# SEN00001.net
KiCad netlist of a schematic drawn in EAGLE
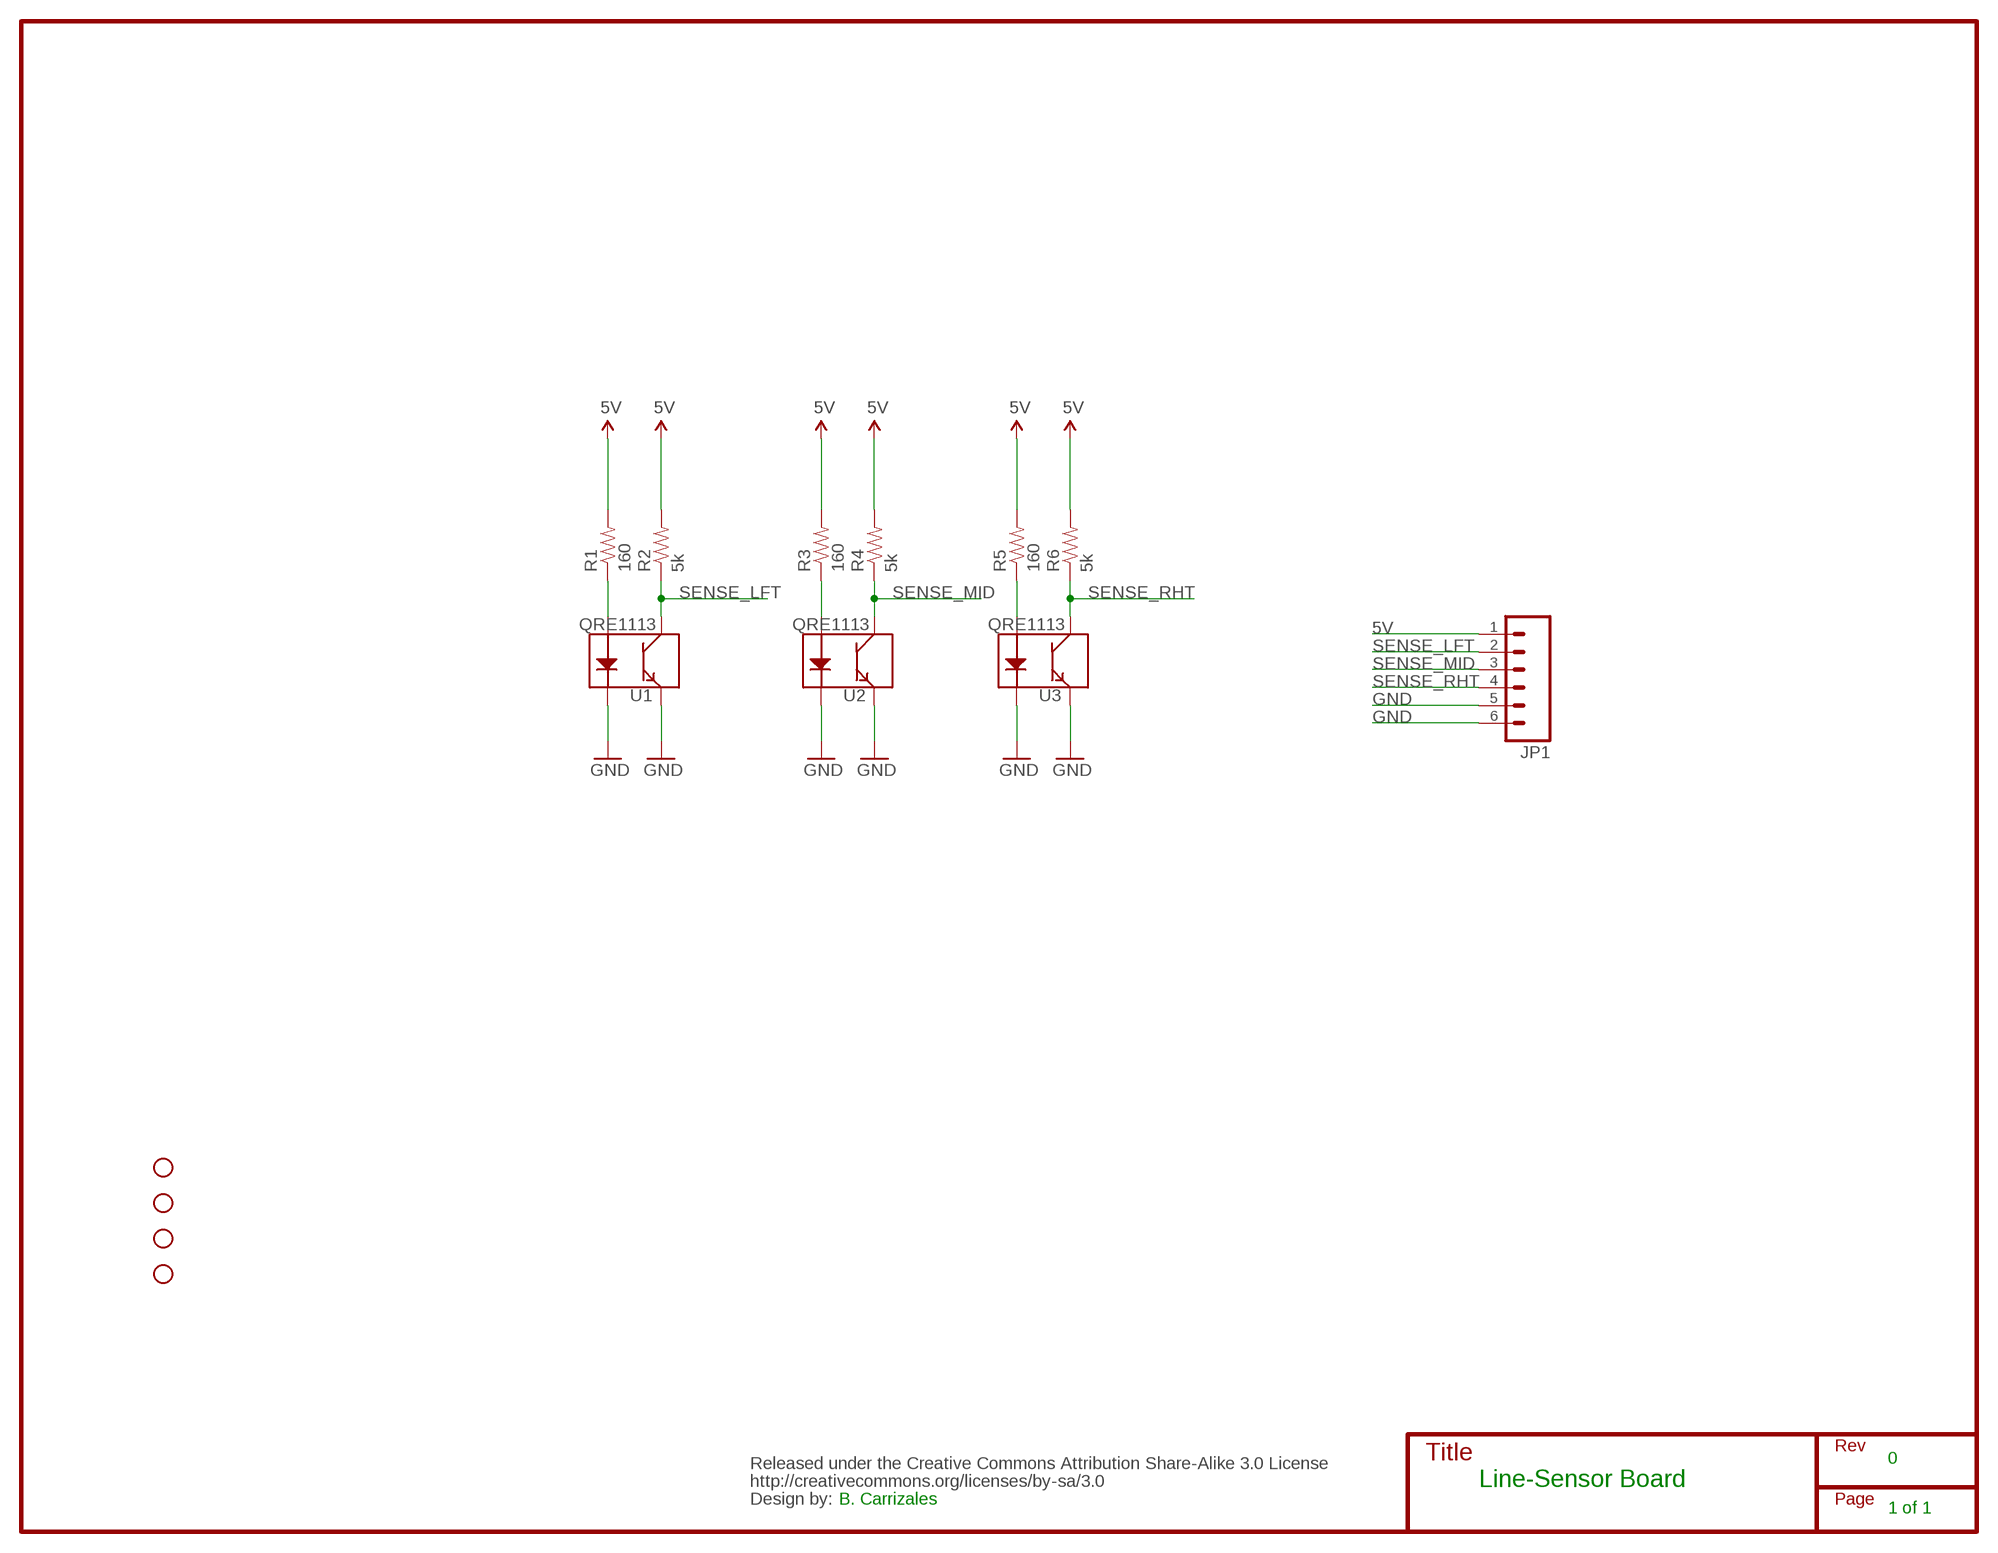
[diagram p0: schematic, sheet 1]

(export (version "E")
  (design (tool "Eeschema 10.0.6"))
  (components
    (comp (ref "CC_TEXT1")
      (value "CREATIVE_COMMONS")
      (footprint "eagle-import:CREATIVE_COMMONS")
      (libsource (lib "eagle-import") (part "CREATIVE_COMMONS"))
    )
    (comp (ref "JP1")
      (value "M06SIP")
      (footprint "eagle-import:1X06")
      (libsource (lib "eagle-import") (part "M06SIP"))
    )
    (comp (ref "R1")
      (value "160")
      (footprint "eagle-import:0603-RES")
      (libsource (lib "eagle-import") (part "RESISTOR0603"))
    )
    (comp (ref "R2")
      (value "5k")
      (footprint "eagle-import:0603-RES")
      (libsource (lib "eagle-import") (part "RESISTOR0603"))
    )
    (comp (ref "R3")
      (value "160")
      (footprint "eagle-import:0603-RES")
      (libsource (lib "eagle-import") (part "RESISTOR0603"))
    )
    (comp (ref "R4")
      (value "5k")
      (footprint "eagle-import:0603-RES")
      (libsource (lib "eagle-import") (part "RESISTOR0603"))
    )
    (comp (ref "R5")
      (value "160")
      (footprint "eagle-import:0603-RES")
      (libsource (lib "eagle-import") (part "RESISTOR0603"))
    )
    (comp (ref "R6")
      (value "5k")
      (footprint "eagle-import:0603-RES")
      (libsource (lib "eagle-import") (part "RESISTOR0603"))
    )
    (comp (ref "STANDOFF1")
      (value "STAND-OFF")
      (footprint "eagle-import:STAND-OFF")
      (libsource (lib "eagle-import") (part "STAND-OFF"))
    )
    (comp (ref "STANDOFF2")
      (value "STAND-OFF")
      (footprint "eagle-import:STAND-OFF")
      (libsource (lib "eagle-import") (part "STAND-OFF"))
    )
    (comp (ref "STANDOFF3")
      (value "STAND-OFF")
      (footprint "eagle-import:STAND-OFF")
      (libsource (lib "eagle-import") (part "STAND-OFF"))
    )
    (comp (ref "STANDOFF4")
      (value "STAND-OFF")
      (footprint "eagle-import:STAND-OFF")
      (libsource (lib "eagle-import") (part "STAND-OFF"))
    )
    (comp (ref "U1")
      (value "QRE1113")
      (footprint "eagle-import:QRE1113")
      (libsource (lib "eagle-import") (part "QRE1113"))
    )
    (comp (ref "U2")
      (value "QRE1113")
      (footprint "eagle-import:QRE1113")
      (libsource (lib "eagle-import") (part "QRE1113"))
    )
    (comp (ref "U3")
      (value "QRE1113")
      (footprint "eagle-import:QRE1113")
      (libsource (lib "eagle-import") (part "QRE1113"))
    )
  )
  (nets
    (net (code "1") (name "/SENSE_LFT") (class "Default")
      (node (ref "JP1") (pin "2") (pinfunction "2_2") (pintype "passive"))
      (node (ref "R2") (pin "1") (pinfunction "1_1") (pintype "passive"))
      (node (ref "U1") (pin "3") (pinfunction "C_3") (pintype "bidirectional"))
    )
    (net (code "2") (name "/SENSE_MID") (class "Default")
      (node (ref "JP1") (pin "3") (pinfunction "3_3") (pintype "passive"))
      (node (ref "R4") (pin "1") (pinfunction "1_1") (pintype "passive"))
      (node (ref "U2") (pin "3") (pinfunction "C_3") (pintype "bidirectional"))
    )
    (net (code "3") (name "/SENSE_RHT") (class "Default")
      (node (ref "JP1") (pin "4") (pinfunction "4_4") (pintype "passive"))
      (node (ref "R6") (pin "1") (pinfunction "1_1") (pintype "passive"))
      (node (ref "U3") (pin "3") (pinfunction "C_3") (pintype "bidirectional"))
    )
    (net (code "4") (name "5V") (class "Default")
      (node (ref "JP1") (pin "1") (pinfunction "1_1") (pintype "passive"))
      (node (ref "R1") (pin "2") (pinfunction "2_2") (pintype "passive"))
      (node (ref "R2") (pin "2") (pinfunction "2_2") (pintype "passive"))
      (node (ref "R3") (pin "2") (pinfunction "2_2") (pintype "passive"))
      (node (ref "R4") (pin "2") (pinfunction "2_2") (pintype "passive"))
      (node (ref "R5") (pin "2") (pinfunction "2_2") (pintype "passive"))
      (node (ref "R6") (pin "2") (pinfunction "2_2") (pintype "passive"))
    )
    (net (code "5") (name "GND") (class "Default")
      (node (ref "JP1") (pin "5") (pinfunction "5_5") (pintype "passive"))
      (node (ref "JP1") (pin "6") (pinfunction "6_6") (pintype "passive"))
      (node (ref "U1") (pin "2") (pinfunction "K_2") (pintype "bidirectional"))
      (node (ref "U1") (pin "4") (pinfunction "E_4") (pintype "bidirectional"))
      (node (ref "U2") (pin "2") (pinfunction "K_2") (pintype "bidirectional"))
      (node (ref "U2") (pin "4") (pinfunction "E_4") (pintype "bidirectional"))
      (node (ref "U3") (pin "2") (pinfunction "K_2") (pintype "bidirectional"))
      (node (ref "U3") (pin "4") (pinfunction "E_4") (pintype "bidirectional"))
    )
    (net (code "6") (name "Net-(U1-A)") (class "Default")
      (node (ref "R1") (pin "1") (pinfunction "1_1") (pintype "passive"))
      (node (ref "U1") (pin "1") (pinfunction "A_1") (pintype "bidirectional"))
    )
    (net (code "7") (name "Net-(U2-A)") (class "Default")
      (node (ref "R3") (pin "1") (pinfunction "1_1") (pintype "passive"))
      (node (ref "U2") (pin "1") (pinfunction "A_1") (pintype "bidirectional"))
    )
    (net (code "8") (name "Net-(U3-A)") (class "Default")
      (node (ref "R5") (pin "1") (pinfunction "1_1") (pintype "passive"))
      (node (ref "U3") (pin "1") (pinfunction "A_1") (pintype "bidirectional"))
    )
  )
)
